# 3_way_uart_switch.net
KiCad netlist of a schematic drawn in Altium Designer
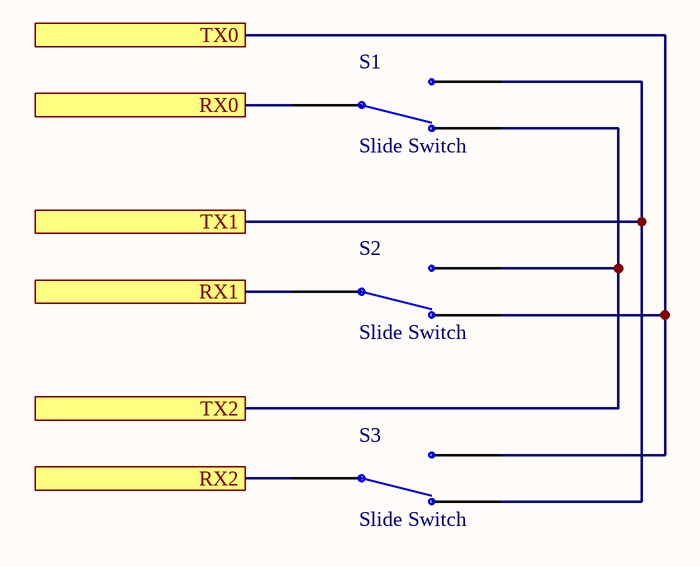
[diagram p0: 3 way uart switch.SchDoc]

(export (version "E")
  (design (tool "Eeschema 10.0.6"))
  (components
    (comp (ref "S1")
      (value "Slide Switch")
      (footprint "CJS Micro switch")
      (libsource (lib "AvionicsParts") (part "Screw Switch"))
    )
    (comp (ref "S2")
      (value "Slide Switch")
      (footprint "CJS Micro switch")
      (libsource (lib "AvionicsParts") (part "Screw Switch"))
    )
    (comp (ref "S3")
      (value "Slide Switch")
      (footprint "CJS Micro switch")
      (libsource (lib "AvionicsParts") (part "Screw Switch"))
    )
  )
  (nets
    (net (code "1") (name "/RX0") (class "Default") (node (ref "S1") (pin "3") (pintype "passive")))
    (net (code "2") (name "/RX1") (class "Default") (node (ref "S2") (pin "3") (pintype "passive")))
    (net (code "3") (name "/RX2") (class "Default") (node (ref "S3") (pin "3") (pintype "passive")))
    (net (code "4") (name "/TX0") (class "Default")
      (node (ref "S2") (pin "1") (pintype "passive"))
      (node (ref "S3") (pin "2") (pintype "passive"))
    )
    (net (code "5") (name "/TX1") (class "Default")
      (node (ref "S1") (pin "2") (pintype "passive"))
      (node (ref "S3") (pin "1") (pintype "passive"))
    )
    (net (code "6") (name "/TX2") (class "Default")
      (node (ref "S1") (pin "1") (pintype "passive"))
      (node (ref "S2") (pin "2") (pintype "passive"))
    )
  )
)
